# SCH_Arduino-Train-v_2_2026-08-09.net
KiCad netlist of a schematic drawn in EasyEDA
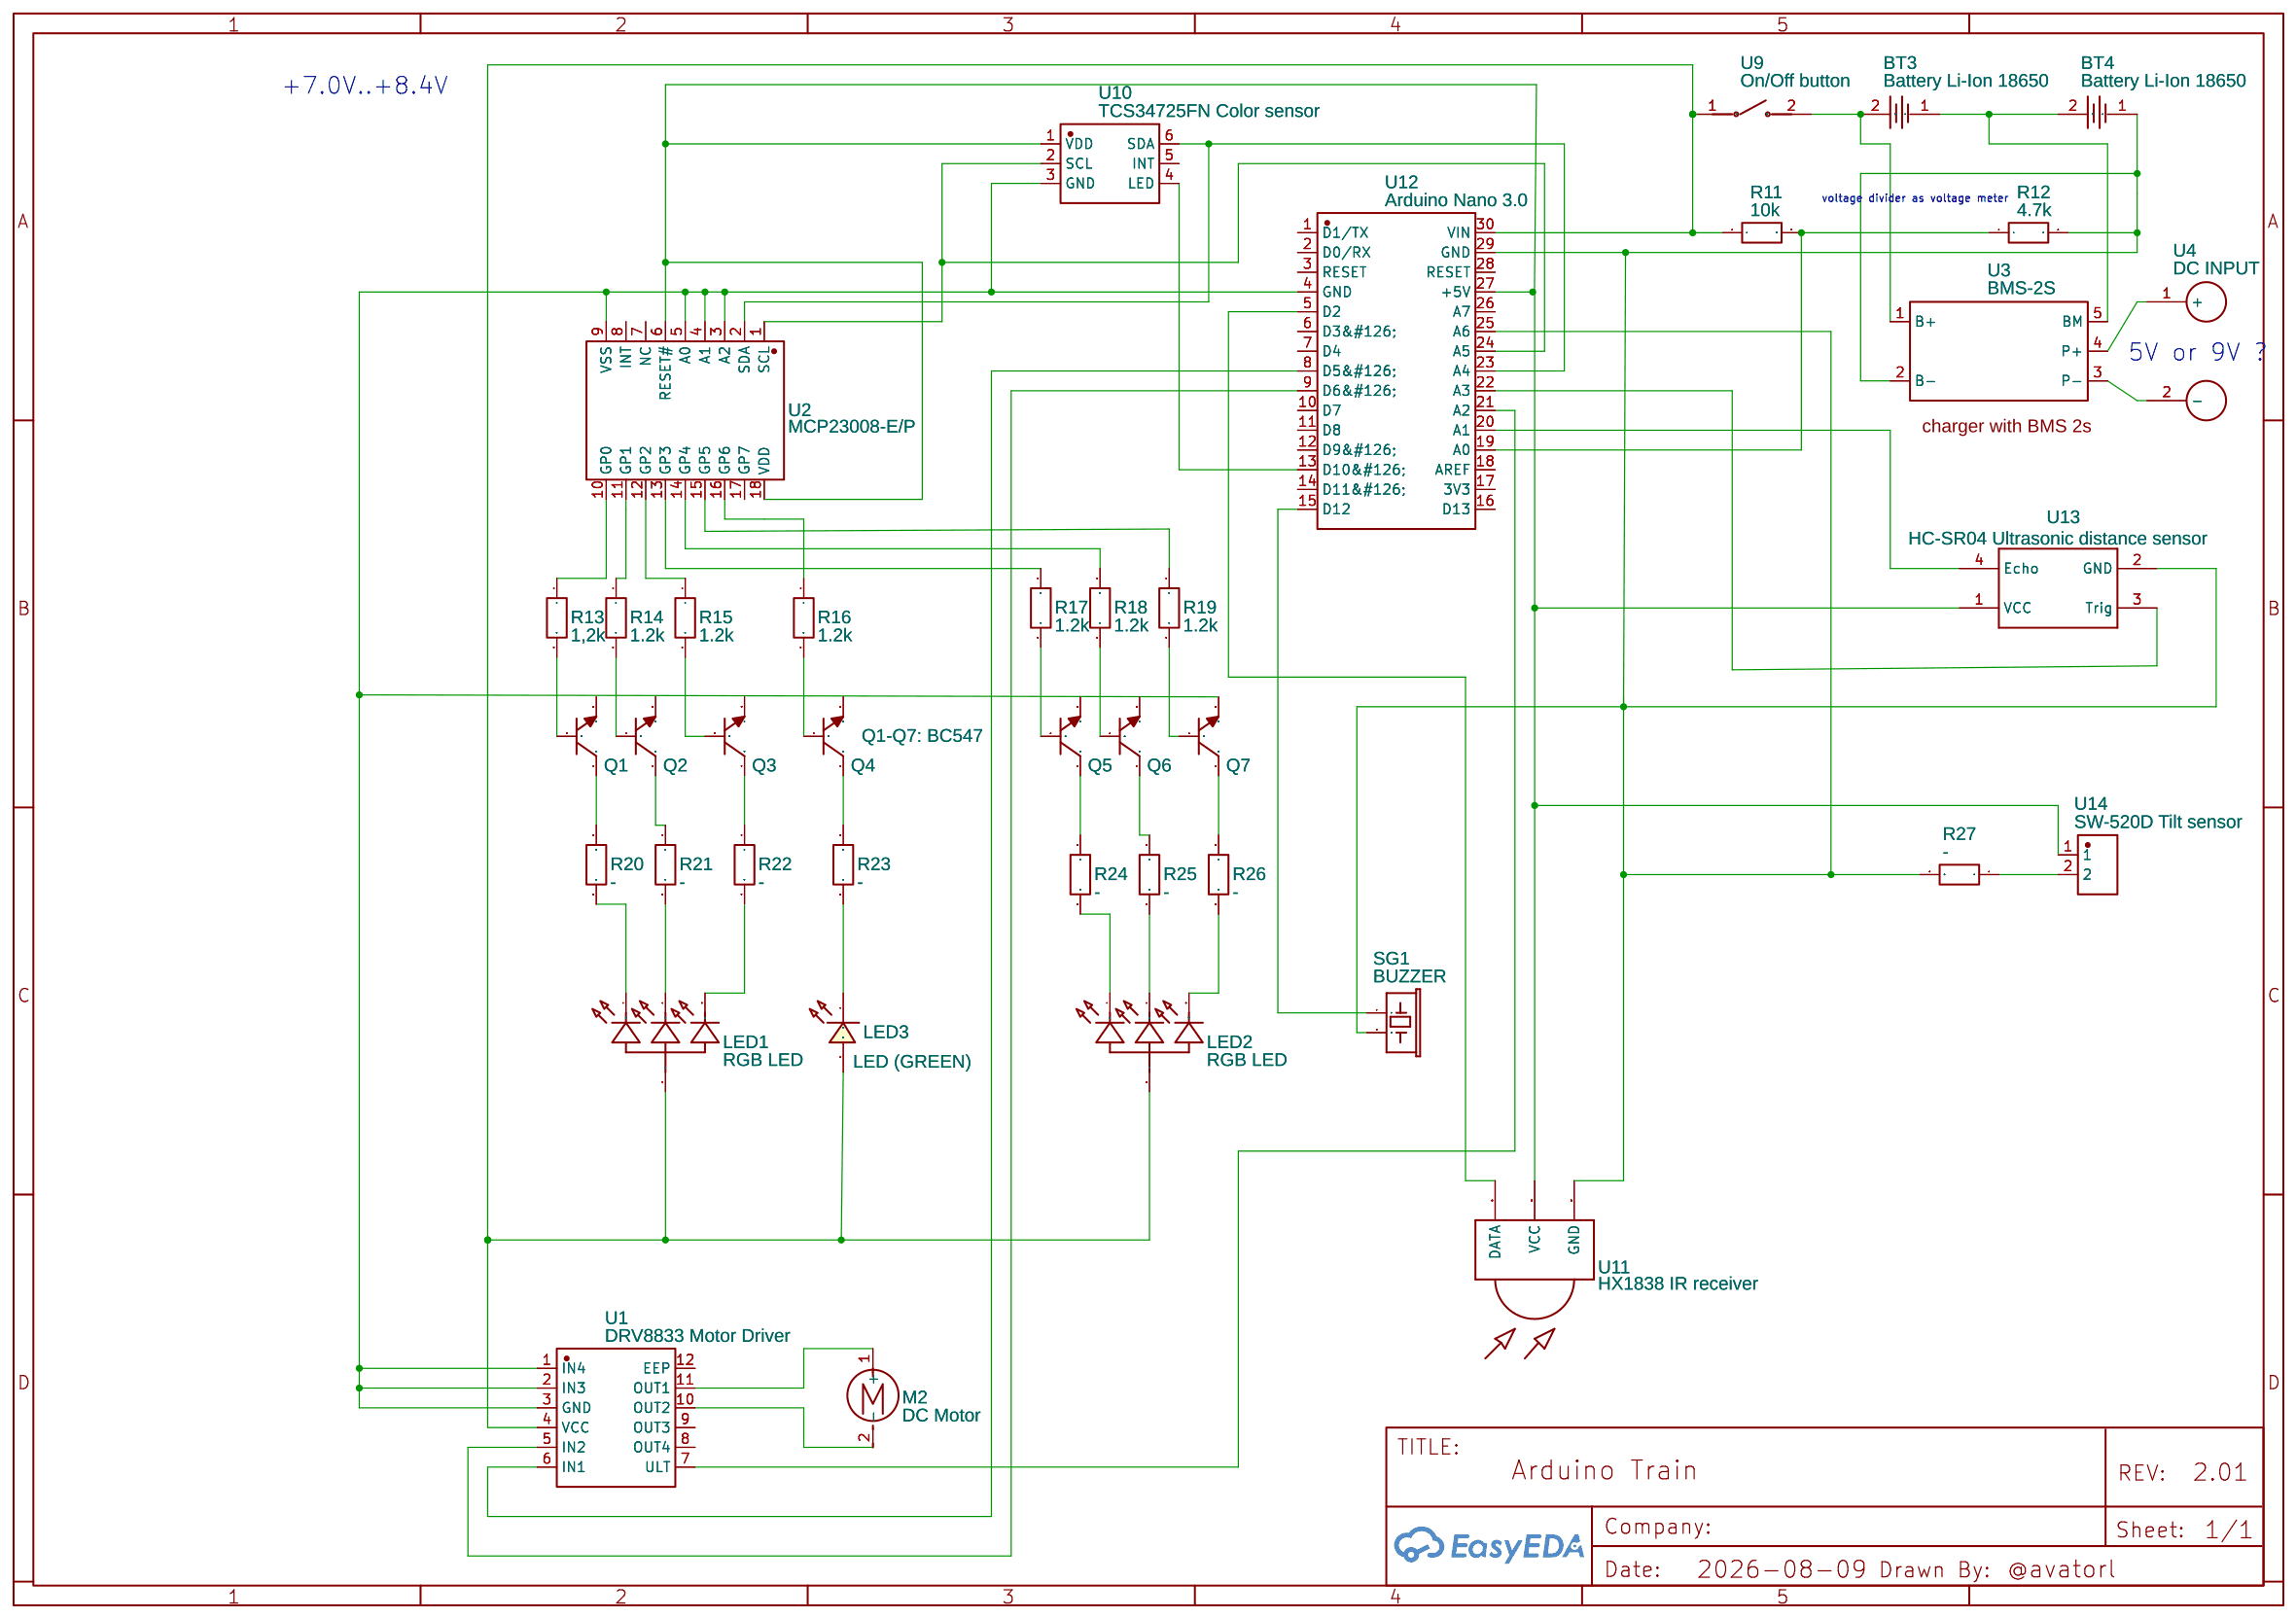
[diagram p0: schematic sheet]

(export (version "E")
  (design (tool "Eeschema 10.0.6"))
  (components
    (comp (ref "BT3")
      (value "Battery Li-Ion 18650")
      (fields
        (field (name "Manufacturer Part") "BH-18650-B1BA002")
        (field (name "Manufacturer") "MYOUNG(美阳)")
      )
      (libsource (lib "") (part "BH-18650-B1BA002"))
    )
    (comp (ref "BT4")
      (value "Battery Li-Ion 18650")
      (fields
        (field (name "Manufacturer Part") "BH-18650-B1BA002")
        (field (name "Manufacturer") "MYOUNG(美阳)")
      )
      (libsource (lib "") (part "BH-18650-B1BA002"))
    )
    (comp (ref "LED1")
      (value "RGB LED")
      (fields (field (name "Manufacturer Part") "3528反贴RGB 6028反贴RGB 缺口蓝色"))
      (libsource (lib "") (part "3528RGB 6028RGB"))
    )
    (comp (ref "LED2")
      (value "RGB LED")
      (fields (field (name "Manufacturer Part") "3528反贴RGB 6028反贴RGB 缺口蓝色"))
      (libsource (lib "") (part "3528RGB 6028RGB"))
    )
    (comp (ref "LED3")
      (value "LED (GREEN)")
      (fields (field (name "Manufacturer Part") "LED三色(Red,Yellow,Green)"))
      (libsource (lib "") (part "LED (GREEN)"))
    )
    (comp (ref "M2") (value "DC Motor") (libsource (lib "") (part "Motor_DC")))
    (comp (ref "Q1")
      (value "Q1-Q7: BC547")
      (fields
        (field (name "Manufacturer Part") "BC547(RANGE:420-800)")
        (field (name "Manufacturer") "CJ(江苏长电/长晶)")
      )
      (libsource (lib "") (part "BC547"))
    )
    (comp (ref "Q2")
      (value "BC547")
      (fields
        (field (name "Manufacturer Part") "BC547(RANGE:420-800)")
        (field (name "Manufacturer") "CJ(江苏长电/长晶)")
      )
      (libsource (lib "") (part "BC547"))
    )
    (comp (ref "Q3")
      (value "BC547")
      (fields
        (field (name "Manufacturer Part") "BC547(RANGE:420-800)")
        (field (name "Manufacturer") "CJ(江苏长电/长晶)")
      )
      (libsource (lib "") (part "BC547"))
    )
    (comp (ref "Q4")
      (value "BC547")
      (fields
        (field (name "Manufacturer Part") "BC547(RANGE:420-800)")
        (field (name "Manufacturer") "CJ(江苏长电/长晶)")
      )
      (libsource (lib "") (part "BC547"))
    )
    (comp (ref "Q5")
      (value "BC547")
      (fields
        (field (name "Manufacturer Part") "BC547(RANGE:420-800)")
        (field (name "Manufacturer") "CJ(江苏长电/长晶)")
      )
      (libsource (lib "") (part "BC547"))
    )
    (comp (ref "Q6")
      (value "BC547")
      (fields
        (field (name "Manufacturer Part") "BC547(RANGE:420-800)")
        (field (name "Manufacturer") "CJ(江苏长电/长晶)")
      )
      (libsource (lib "") (part "BC547"))
    )
    (comp (ref "Q7")
      (value "BC547")
      (fields
        (field (name "Manufacturer Part") "BC547(RANGE:420-800)")
        (field (name "Manufacturer") "CJ(江苏长电/长晶)")
      )
      (libsource (lib "") (part "BC547"))
    )
    (comp (ref "R11") (value "10k") (libsource (lib "") (part "R_0603_EU_1")))
    (comp (ref "R12") (value "4.7k") (libsource (lib "") (part "R_0603_EU_1")))
    (comp (ref "R13") (value "1,2k") (libsource (lib "") (part "R_0603_EU")))
    (comp (ref "R14") (value "1.2k") (libsource (lib "") (part "R_0603_EU")))
    (comp (ref "R15") (value "1.2k") (libsource (lib "") (part "R_0603_EU")))
    (comp (ref "R16") (value "1.2k") (libsource (lib "") (part "R_0603_EU")))
    (comp (ref "R17") (value "1.2k") (libsource (lib "") (part "R_0603_EU")))
    (comp (ref "R18") (value "1.2k") (libsource (lib "") (part "R_0603_EU")))
    (comp (ref "R19") (value "1.2k") (libsource (lib "") (part "R_0603_EU")))
    (comp (ref "R20") (value "-") (libsource (lib "") (part "R_0603_EU")))
    (comp (ref "R21") (value "-") (libsource (lib "") (part "R_0603_EU")))
    (comp (ref "R22") (value "-") (libsource (lib "") (part "R_0603_EU")))
    (comp (ref "R23") (value "-") (libsource (lib "") (part "R_0603_EU")))
    (comp (ref "R24") (value "-") (libsource (lib "") (part "R_0603_EU")))
    (comp (ref "R25") (value "-") (libsource (lib "") (part "R_0603_EU")))
    (comp (ref "R26") (value "-") (libsource (lib "") (part "R_0603_EU")))
    (comp (ref "R27") (value "-") (libsource (lib "") (part "R_0603_EU_2")))
    (comp (ref "SG1") (value "BUZZER") (libsource (lib "") (part "BUZZER")))
    (comp (ref "U1")
      (value "DRV8833 Motor Driver")
      (fields (field (name "Manufacturer Part") "DRV8833"))
      (libsource (lib "") (part "DRV8833 - Motor Driver"))
    )
    (comp (ref "U2")
      (value "MCP23008-E/P")
      (fields (field (name "Manufacturer") "MICROCHIP(美国微芯)"))
      (libsource (lib "") (part "MCP23008-E/P"))
    )
    (comp (ref "U3")
      (value "BMS-2S")
      (fields (field (name "Manufacturer Part") "HX-2S-D01"))
      (libsource (lib "") (part "2S 3A-10A Lithium Li-ion 18650 Battery BMS Protection PCB Board 7.4v/8.4V"))
    )
    (comp (ref "U4") (value "DC INPUT") (libsource (lib "") (part "DC INPUT")))
    (comp (ref "U9")
      (value "On/Off button")
      (fields (field (name "Manufacturer Part") "BUTTON"))
      (libsource (lib "") (part "BUTTON"))
    )
    (comp (ref "U10")
      (value "TCS34725FN Color sensor")
      (fields (field (name "Manufacturer Part") "TCS34725FN") (field (name "Manufacturer") "ams(艾迈斯半导体)"))
      (libsource (lib "") (part "TCS34725FN"))
    )
    (comp (ref "U11") (value "HX1838 IR receiver") (libsource (lib "") (part "IR_HX1838")))
    (comp (ref "U12")
      (value "Arduino Nano 3.0")
      (fields (field (name "Manufacturer Part") "ARDUINO_NANO"))
      (libsource (lib "") (part "ARDUINO_NANO"))
    )
    (comp (ref "U13")
      (value "HC-SR04 Ultrasonic distance sensor")
      (libsource (lib "") (part "SPM0204UD5SMD"))
    )
    (comp (ref "U14")
      (value "SW-520D Tilt sensor")
      (fields (field (name "Manufacturer Part") "SW-520D") (field (name "Manufacturer") "SHOU HAN(首韩)"))
      (libsource (lib "") (part "SW-520D"))
    )
  )
  (nets
    (net (code "1") (name "Net-(LED1-A)") (class "Default")
      (node (ref "LED1") (pin "3") (pinfunction "A_3") (pintype "unspecified"))
      (node (ref "LED2") (pin "3") (pinfunction "A_3") (pintype "unspecified"))
      (node (ref "LED3") (pin "2") (pinfunction "2_2") (pintype "unspecified"))
      (node (ref "R11") (pin "1") (pinfunction "1_1") (pintype "unspecified"))
      (node (ref "U1") (pin "4") (pinfunction "VCC_4") (pintype "unspecified"))
      (node (ref "U12") (pin "30") (pinfunction "VIN_30") (pintype "unspecified"))
      (node (ref "U9") (pin "1") (pinfunction "1_1") (pintype "unspecified"))
    )
    (net (code "2") (name "Net-(LED1-B)") (class "Default")
      (node (ref "LED1") (pin "1") (pinfunction "B_1") (pintype "unspecified"))
      (node (ref "R21") (pin "2") (pinfunction "2_2") (pintype "unspecified"))
    )
    (net (code "3") (name "Net-(LED1-G)") (class "Default")
      (node (ref "LED1") (pin "4") (pinfunction "G_4") (pintype "unspecified"))
      (node (ref "R20") (pin "2") (pinfunction "2_2") (pintype "unspecified"))
    )
    (net (code "4") (name "Net-(LED1-R)") (class "Default")
      (node (ref "LED1") (pin "2") (pinfunction "R_2") (pintype "unspecified"))
      (node (ref "R22") (pin "2") (pinfunction "2_2") (pintype "unspecified"))
    )
    (net (code "5") (name "Net-(LED2-B)") (class "Default")
      (node (ref "LED2") (pin "1") (pinfunction "B_1") (pintype "unspecified"))
      (node (ref "R25") (pin "2") (pinfunction "2_2") (pintype "unspecified"))
    )
    (net (code "6") (name "Net-(LED2-G)") (class "Default")
      (node (ref "LED2") (pin "4") (pinfunction "G_4") (pintype "unspecified"))
      (node (ref "R24") (pin "2") (pinfunction "2_2") (pintype "unspecified"))
    )
    (net (code "7") (name "Net-(LED2-R)") (class "Default")
      (node (ref "LED2") (pin "2") (pinfunction "R_2") (pintype "unspecified"))
      (node (ref "R26") (pin "2") (pinfunction "2_2") (pintype "unspecified"))
    )
    (net (code "8") (name "Net-(LED3-Pad1)") (class "Default")
      (node (ref "LED3") (pin "1") (pinfunction "1_1") (pintype "unspecified"))
      (node (ref "R23") (pin "2") (pinfunction "2_2") (pintype "unspecified"))
    )
    (net (code "9") (name "Net-(M2-+)") (class "Default")
      (node (ref "M2") (pin "1") (pinfunction "+_1") (pintype "unspecified"))
      (node (ref "U1") (pin "11") (pinfunction "OUT1_11") (pintype "unspecified"))
    )
    (net (code "10") (name "Net-(M2--)") (class "Default")
      (node (ref "M2") (pin "2") (pinfunction "-_2") (pintype "unspecified"))
      (node (ref "U1") (pin "10") (pinfunction "OUT2_10") (pintype "unspecified"))
    )
    (net (code "11") (name "Net-(Q1-B)") (class "Default")
      (node (ref "Q1") (pin "2") (pinfunction "B_2") (pintype "unspecified"))
      (node (ref "R13") (pin "2") (pinfunction "2_2") (pintype "unspecified"))
    )
    (net (code "12") (name "Net-(Q1-C)") (class "Default")
      (node (ref "Q1") (pin "1") (pinfunction "C_1") (pintype "unspecified"))
      (node (ref "R20") (pin "1") (pinfunction "1_1") (pintype "unspecified"))
    )
    (net (code "13") (name "Net-(Q2-B)") (class "Default")
      (node (ref "Q2") (pin "2") (pinfunction "B_2") (pintype "unspecified"))
      (node (ref "R14") (pin "2") (pinfunction "2_2") (pintype "unspecified"))
    )
    (net (code "14") (name "Net-(Q2-C)") (class "Default")
      (node (ref "Q2") (pin "1") (pinfunction "C_1") (pintype "unspecified"))
      (node (ref "R21") (pin "1") (pinfunction "1_1") (pintype "unspecified"))
    )
    (net (code "15") (name "Net-(Q3-B)") (class "Default")
      (node (ref "Q3") (pin "2") (pinfunction "B_2") (pintype "unspecified"))
      (node (ref "R15") (pin "2") (pinfunction "2_2") (pintype "unspecified"))
    )
    (net (code "16") (name "Net-(Q3-C)") (class "Default")
      (node (ref "Q3") (pin "1") (pinfunction "C_1") (pintype "unspecified"))
      (node (ref "R22") (pin "1") (pinfunction "1_1") (pintype "unspecified"))
    )
    (net (code "17") (name "Net-(Q4-B)") (class "Default")
      (node (ref "Q4") (pin "2") (pinfunction "B_2") (pintype "unspecified"))
      (node (ref "R16") (pin "2") (pinfunction "2_2") (pintype "unspecified"))
    )
    (net (code "18") (name "Net-(Q4-C)") (class "Default")
      (node (ref "Q4") (pin "1") (pinfunction "C_1") (pintype "unspecified"))
      (node (ref "R23") (pin "1") (pinfunction "1_1") (pintype "unspecified"))
    )
    (net (code "19") (name "Net-(Q5-B)") (class "Default")
      (node (ref "Q5") (pin "2") (pinfunction "B_2") (pintype "unspecified"))
      (node (ref "R17") (pin "2") (pinfunction "2_2") (pintype "unspecified"))
    )
    (net (code "20") (name "Net-(Q5-C)") (class "Default")
      (node (ref "Q5") (pin "1") (pinfunction "C_1") (pintype "unspecified"))
      (node (ref "R24") (pin "1") (pinfunction "1_1") (pintype "unspecified"))
    )
    (net (code "21") (name "Net-(Q6-B)") (class "Default")
      (node (ref "Q6") (pin "2") (pinfunction "B_2") (pintype "unspecified"))
      (node (ref "R18") (pin "2") (pinfunction "2_2") (pintype "unspecified"))
    )
    (net (code "22") (name "Net-(Q6-C)") (class "Default")
      (node (ref "Q6") (pin "1") (pinfunction "C_1") (pintype "unspecified"))
      (node (ref "R25") (pin "1") (pinfunction "1_1") (pintype "unspecified"))
    )
    (net (code "23") (name "Net-(Q7-B)") (class "Default")
      (node (ref "Q7") (pin "2") (pinfunction "B_2") (pintype "unspecified"))
      (node (ref "R19") (pin "2") (pinfunction "2_2") (pintype "unspecified"))
    )
    (net (code "24") (name "Net-(Q7-C)") (class "Default")
      (node (ref "Q7") (pin "1") (pinfunction "C_1") (pintype "unspecified"))
      (node (ref "R26") (pin "1") (pinfunction "1_1") (pintype "unspecified"))
    )
    (net (code "25") (name "Net-(Q7-E)") (class "Default")
      (node (ref "Q7") (pin "3") (pinfunction "E_3") (pintype "unspecified"))
      (node (ref "U1") (pin "1") (pinfunction "IN4_1") (pintype "unspecified"))
      (node (ref "U1") (pin "2") (pinfunction "IN3_2") (pintype "unspecified"))
      (node (ref "U1") (pin "3") (pinfunction "GND_3") (pintype "unspecified"))
      (node (ref "U10") (pin "3") (pinfunction "GND_3") (pintype "unspecified"))
      (node (ref "U12") (pin "4") (pinfunction "GND_4") (pintype "unspecified"))
      (node (ref "U2") (pin "3") (pinfunction "A2_3") (pintype "unspecified"))
      (node (ref "U2") (pin "4") (pinfunction "A1_4") (pintype "unspecified"))
      (node (ref "U2") (pin "5") (pinfunction "A0_5") (pintype "unspecified"))
      (node (ref "U2") (pin "9") (pinfunction "VSS_9") (pintype "unspecified"))
    )
    (net (code "26") (name "Net-(R27-Pad1)") (class "Default")
      (node (ref "R27") (pin "1") (pinfunction "1_1") (pintype "unspecified"))
      (node (ref "U14") (pin "2") (pinfunction "2_2") (pintype "unspecified"))
    )
    (net (code "27") (name "Net-(U1-IN1)") (class "Default")
      (node (ref "U1") (pin "6") (pinfunction "IN1_6") (pintype "unspecified"))
      (node (ref "U12") (pin "8") (pinfunction "D5&#126;_8") (pintype "unspecified"))
    )
    (net (code "28") (name "Net-(U1-IN2)") (class "Default")
      (node (ref "U1") (pin "5") (pinfunction "IN2_5") (pintype "unspecified"))
      (node (ref "U12") (pin "9") (pinfunction "D6&#126;_9") (pintype "unspecified"))
    )
    (net (code "29") (name "Net-(U1-ULT)") (class "Default")
      (node (ref "U1") (pin "7") (pinfunction "ULT_7") (pintype "unspecified"))
      (node (ref "U12") (pin "21") (pinfunction "A2_21") (pintype "unspecified"))
    )
    (net (code "30") (name "Net-(U2-GP0)") (class "Default")
      (node (ref "R13") (pin "1") (pinfunction "1_1") (pintype "unspecified"))
      (node (ref "U2") (pin "10") (pinfunction "GP0_10") (pintype "unspecified"))
    )
    (net (code "31") (name "Net-(U2-GP1)") (class "Default")
      (node (ref "R14") (pin "1") (pinfunction "1_1") (pintype "unspecified"))
      (node (ref "U2") (pin "11") (pinfunction "GP1_11") (pintype "unspecified"))
    )
    (net (code "32") (name "Net-(U2-GP2)") (class "Default")
      (node (ref "R15") (pin "1") (pinfunction "1_1") (pintype "unspecified"))
      (node (ref "U2") (pin "12") (pinfunction "GP2_12") (pintype "unspecified"))
    )
    (net (code "33") (name "Net-(U2-GP3)") (class "Default")
      (node (ref "R17") (pin "1") (pinfunction "1_1") (pintype "unspecified"))
      (node (ref "U2") (pin "13") (pinfunction "GP3_13") (pintype "unspecified"))
    )
    (net (code "34") (name "Net-(U2-GP4)") (class "Default")
      (node (ref "R18") (pin "1") (pinfunction "1_1") (pintype "unspecified"))
      (node (ref "U2") (pin "14") (pinfunction "GP4_14") (pintype "unspecified"))
    )
    (net (code "35") (name "Net-(U2-GP5)") (class "Default")
      (node (ref "R19") (pin "1") (pinfunction "1_1") (pintype "unspecified"))
      (node (ref "U2") (pin "15") (pinfunction "GP5_15") (pintype "unspecified"))
    )
    (net (code "36") (name "Net-(U2-GP6)") (class "Default")
      (node (ref "R16") (pin "1") (pinfunction "1_1") (pintype "unspecified"))
      (node (ref "U2") (pin "16") (pinfunction "GP6_16") (pintype "unspecified"))
    )
    (net (code "37") (name "Net-(U3-B+)") (class "Default")
      (node (ref "BT3") (pin "2") (pinfunction "2_2") (pintype "input"))
      (node (ref "U3") (pin "1") (pinfunction "B+_1") (pintype "unspecified"))
      (node (ref "U9") (pin "2") (pinfunction "2_2") (pintype "unspecified"))
    )
    (net (code "38") (name "Net-(U3-BM)") (class "Default")
      (node (ref "BT3") (pin "1") (pinfunction "1_1") (pintype "input"))
      (node (ref "BT4") (pin "2") (pinfunction "2_2") (pintype "input"))
      (node (ref "U3") (pin "5") (pinfunction "BM_5") (pintype "unspecified"))
    )
    (net (code "39") (name "Net-(U3-P+)") (class "Default")
      (node (ref "U3") (pin "4") (pinfunction "P+_4") (pintype "unspecified"))
      (node (ref "U4") (pin "1") (pinfunction "+_1") (pintype "unspecified"))
    )
    (net (code "40") (name "Net-(U3-P-)") (class "Default")
      (node (ref "U3") (pin "3") (pinfunction "P-_3") (pintype "unspecified"))
      (node (ref "U4") (pin "2") (pinfunction "-_2") (pintype "unspecified"))
    )
    (net (code "41") (name "Net-(U10-LED)") (class "Default")
      (node (ref "U10") (pin "4") (pinfunction "LED_4") (pintype "unspecified"))
      (node (ref "U12") (pin "13") (pinfunction "D10&#126;_13") (pintype "unspecified"))
    )
    (net (code "42") (name "Net-(U10-SCL)") (class "Default")
      (node (ref "U10") (pin "2") (pinfunction "SCL_2") (pintype "unspecified"))
      (node (ref "U12") (pin "24") (pinfunction "A5_24") (pintype "unspecified"))
      (node (ref "U2") (pin "1") (pinfunction "SCL_1") (pintype "unspecified"))
    )
    (net (code "43") (name "Net-(U10-SDA)") (class "Default")
      (node (ref "U10") (pin "6") (pinfunction "SDA_6") (pintype "unspecified"))
      (node (ref "U12") (pin "23") (pinfunction "A4_23") (pintype "unspecified"))
      (node (ref "U2") (pin "2") (pinfunction "SDA_2") (pintype "unspecified"))
    )
    (net (code "44") (name "Net-(U10-VDD)") (class "Default")
      (node (ref "U10") (pin "1") (pinfunction "VDD_1") (pintype "unspecified"))
      (node (ref "U11") (pin "VCC") (pinfunction "VCC_VCC") (pintype "unspecified"))
      (node (ref "U12") (pin "27") (pinfunction "+5V_27") (pintype "unspecified"))
      (node (ref "U13") (pin "1") (pinfunction "VCC_1") (pintype "unspecified"))
      (node (ref "U14") (pin "1") (pinfunction "1_1") (pintype "unspecified"))
      (node (ref "U2") (pin "18") (pinfunction "VDD_18") (pintype "unspecified"))
      (node (ref "U2") (pin "6") (pinfunction "RESET#_6") (pintype "unspecified"))
    )
    (net (code "45") (name "Net-(U12-A0)") (class "Default")
      (node (ref "R11") (pin "2") (pinfunction "2_2") (pintype "unspecified"))
      (node (ref "R12") (pin "1") (pinfunction "1_1") (pintype "unspecified"))
      (node (ref "U12") (pin "19") (pinfunction "A0_19") (pintype "unspecified"))
    )
    (net (code "46") (name "Net-(U12-A1)") (class "Default")
      (node (ref "U12") (pin "20") (pinfunction "A1_20") (pintype "unspecified"))
      (node (ref "U13") (pin "4") (pinfunction "Echo_4") (pintype "unspecified"))
    )
    (net (code "47") (name "Net-(U12-A3)") (class "Default")
      (node (ref "U12") (pin "22") (pinfunction "A3_22") (pintype "unspecified"))
      (node (ref "U13") (pin "3") (pinfunction "Trig_3") (pintype "unspecified"))
    )
    (net (code "48") (name "Net-(U12-A6)") (class "Default")
      (node (ref "BT4") (pin "1") (pinfunction "1_1") (pintype "input"))
      (node (ref "R12") (pin "2") (pinfunction "2_2") (pintype "unspecified"))
      (node (ref "R27") (pin "2") (pinfunction "2_2") (pintype "unspecified"))
      (node (ref "SG1") (pin "2") (pinfunction "2_2") (pintype "unspecified"))
      (node (ref "U11") (pin "GND") (pinfunction "GND_GND") (pintype "unspecified"))
      (node (ref "U12") (pin "25") (pinfunction "A6_25") (pintype "unspecified"))
      (node (ref "U12") (pin "29") (pinfunction "GND_29") (pintype "unspecified"))
      (node (ref "U13") (pin "2") (pinfunction "GND_2") (pintype "unspecified"))
      (node (ref "U3") (pin "2") (pinfunction "B-_2") (pintype "unspecified"))
    )
    (net (code "49") (name "Net-(U12-D2)") (class "Default")
      (node (ref "U11") (pin "DATA") (pinfunction "DATA_DATA") (pintype "unspecified"))
      (node (ref "U12") (pin "5") (pinfunction "D2_5") (pintype "unspecified"))
    )
    (net (code "50") (name "Net-(U12-D12)") (class "Default")
      (node (ref "SG1") (pin "1") (pinfunction "1_1") (pintype "unspecified"))
      (node (ref "U12") (pin "15") (pinfunction "D12_15") (pintype "unspecified"))
    )
    (net (code "51") (name "unconnected-(Q1-E-Pad3)") (class "Default")
      (node (ref "Q1") (pin "3") (pinfunction "E_3") (pintype "unspecified"))
    )
    (net (code "52") (name "unconnected-(Q2-E-Pad3)") (class "Default")
      (node (ref "Q2") (pin "3") (pinfunction "E_3") (pintype "unspecified"))
    )
    (net (code "53") (name "unconnected-(Q3-E-Pad3)") (class "Default")
      (node (ref "Q3") (pin "3") (pinfunction "E_3") (pintype "unspecified"))
    )
    (net (code "54") (name "unconnected-(Q4-E-Pad3)") (class "Default")
      (node (ref "Q4") (pin "3") (pinfunction "E_3") (pintype "unspecified"))
    )
    (net (code "55") (name "unconnected-(Q5-E-Pad3)") (class "Default")
      (node (ref "Q5") (pin "3") (pinfunction "E_3") (pintype "unspecified"))
    )
    (net (code "56") (name "unconnected-(Q6-E-Pad3)") (class "Default")
      (node (ref "Q6") (pin "3") (pinfunction "E_3") (pintype "unspecified"))
    )
    (net (code "57") (name "unconnected-(U1-EEP-Pad12)") (class "Default")
      (node (ref "U1") (pin "12") (pinfunction "EEP_12") (pintype "unspecified"))
    )
    (net (code "58") (name "unconnected-(U1-OUT3-Pad9)") (class "Default")
      (node (ref "U1") (pin "9") (pinfunction "OUT3_9") (pintype "unspecified"))
    )
    (net (code "59") (name "unconnected-(U1-OUT4-Pad8)") (class "Default")
      (node (ref "U1") (pin "8") (pinfunction "OUT4_8") (pintype "unspecified"))
    )
    (net (code "60") (name "unconnected-(U2-GP7-Pad17)") (class "Default")
      (node (ref "U2") (pin "17") (pinfunction "GP7_17") (pintype "unspecified"))
    )
    (net (code "61") (name "unconnected-(U2-INT-Pad8)") (class "Default")
      (node (ref "U2") (pin "8") (pinfunction "INT_8") (pintype "unspecified"))
    )
    (net (code "62") (name "unconnected-(U2-NC-Pad7)") (class "Default")
      (node (ref "U2") (pin "7") (pinfunction "NC_7") (pintype "unspecified"))
    )
    (net (code "63") (name "unconnected-(U10-INT-Pad5)") (class "Default")
      (node (ref "U10") (pin "5") (pinfunction "INT_5") (pintype "unspecified"))
    )
    (net (code "64") (name "unconnected-(U12-3V3-Pad17)") (class "Default")
      (node (ref "U12") (pin "17") (pinfunction "3V3_17") (pintype "unspecified"))
    )
    (net (code "65") (name "unconnected-(U12-A7-Pad26)") (class "Default")
      (node (ref "U12") (pin "26") (pinfunction "A7_26") (pintype "unspecified"))
    )
    (net (code "66") (name "unconnected-(U12-AREF-Pad18)") (class "Default")
      (node (ref "U12") (pin "18") (pinfunction "AREF_18") (pintype "unspecified"))
    )
    (net (code "67") (name "unconnected-(U12-D0{slash}RX-Pad2)") (class "Default")
      (node (ref "U12") (pin "2") (pinfunction "D0/RX_2") (pintype "unspecified"))
    )
    (net (code "68") (name "unconnected-(U12-D1{slash}TX-Pad1)") (class "Default")
      (node (ref "U12") (pin "1") (pinfunction "D1/TX_1") (pintype "unspecified"))
    )
    (net (code "69") (name "unconnected-(U12-D3&#126;-Pad6)") (class "Default")
      (node (ref "U12") (pin "6") (pinfunction "D3&#126;_6") (pintype "unspecified"))
    )
    (net (code "70") (name "unconnected-(U12-D4-Pad7)") (class "Default")
      (node (ref "U12") (pin "7") (pinfunction "D4_7") (pintype "unspecified"))
    )
    (net (code "71") (name "unconnected-(U12-D7-Pad10)") (class "Default")
      (node (ref "U12") (pin "10") (pinfunction "D7_10") (pintype "unspecified"))
    )
    (net (code "72") (name "unconnected-(U12-D8-Pad11)") (class "Default")
      (node (ref "U12") (pin "11") (pinfunction "D8_11") (pintype "unspecified"))
    )
    (net (code "73") (name "unconnected-(U12-D9&#126;-Pad12)") (class "Default")
      (node (ref "U12") (pin "12") (pinfunction "D9&#126;_12") (pintype "unspecified"))
    )
    (net (code "74") (name "unconnected-(U12-D11&#126;-Pad14)") (class "Default")
      (node (ref "U12") (pin "14") (pinfunction "D11&#126;_14") (pintype "unspecified"))
    )
    (net (code "75") (name "unconnected-(U12-D13-Pad16)") (class "Default")
      (node (ref "U12") (pin "16") (pinfunction "D13_16") (pintype "unspecified"))
    )
    (net (code "76") (name "unconnected-(U12-RESET-Pad3)") (class "Default")
      (node (ref "U12") (pin "3") (pinfunction "RESET_3") (pintype "unspecified"))
    )
    (net (code "77") (name "unconnected-(U12-RESET-Pad28)") (class "Default")
      (node (ref "U12") (pin "28") (pinfunction "RESET_28") (pintype "unspecified"))
    )
  )
)
